# laser-tag.net
KiCad netlist of a schematic drawn in EAGLE
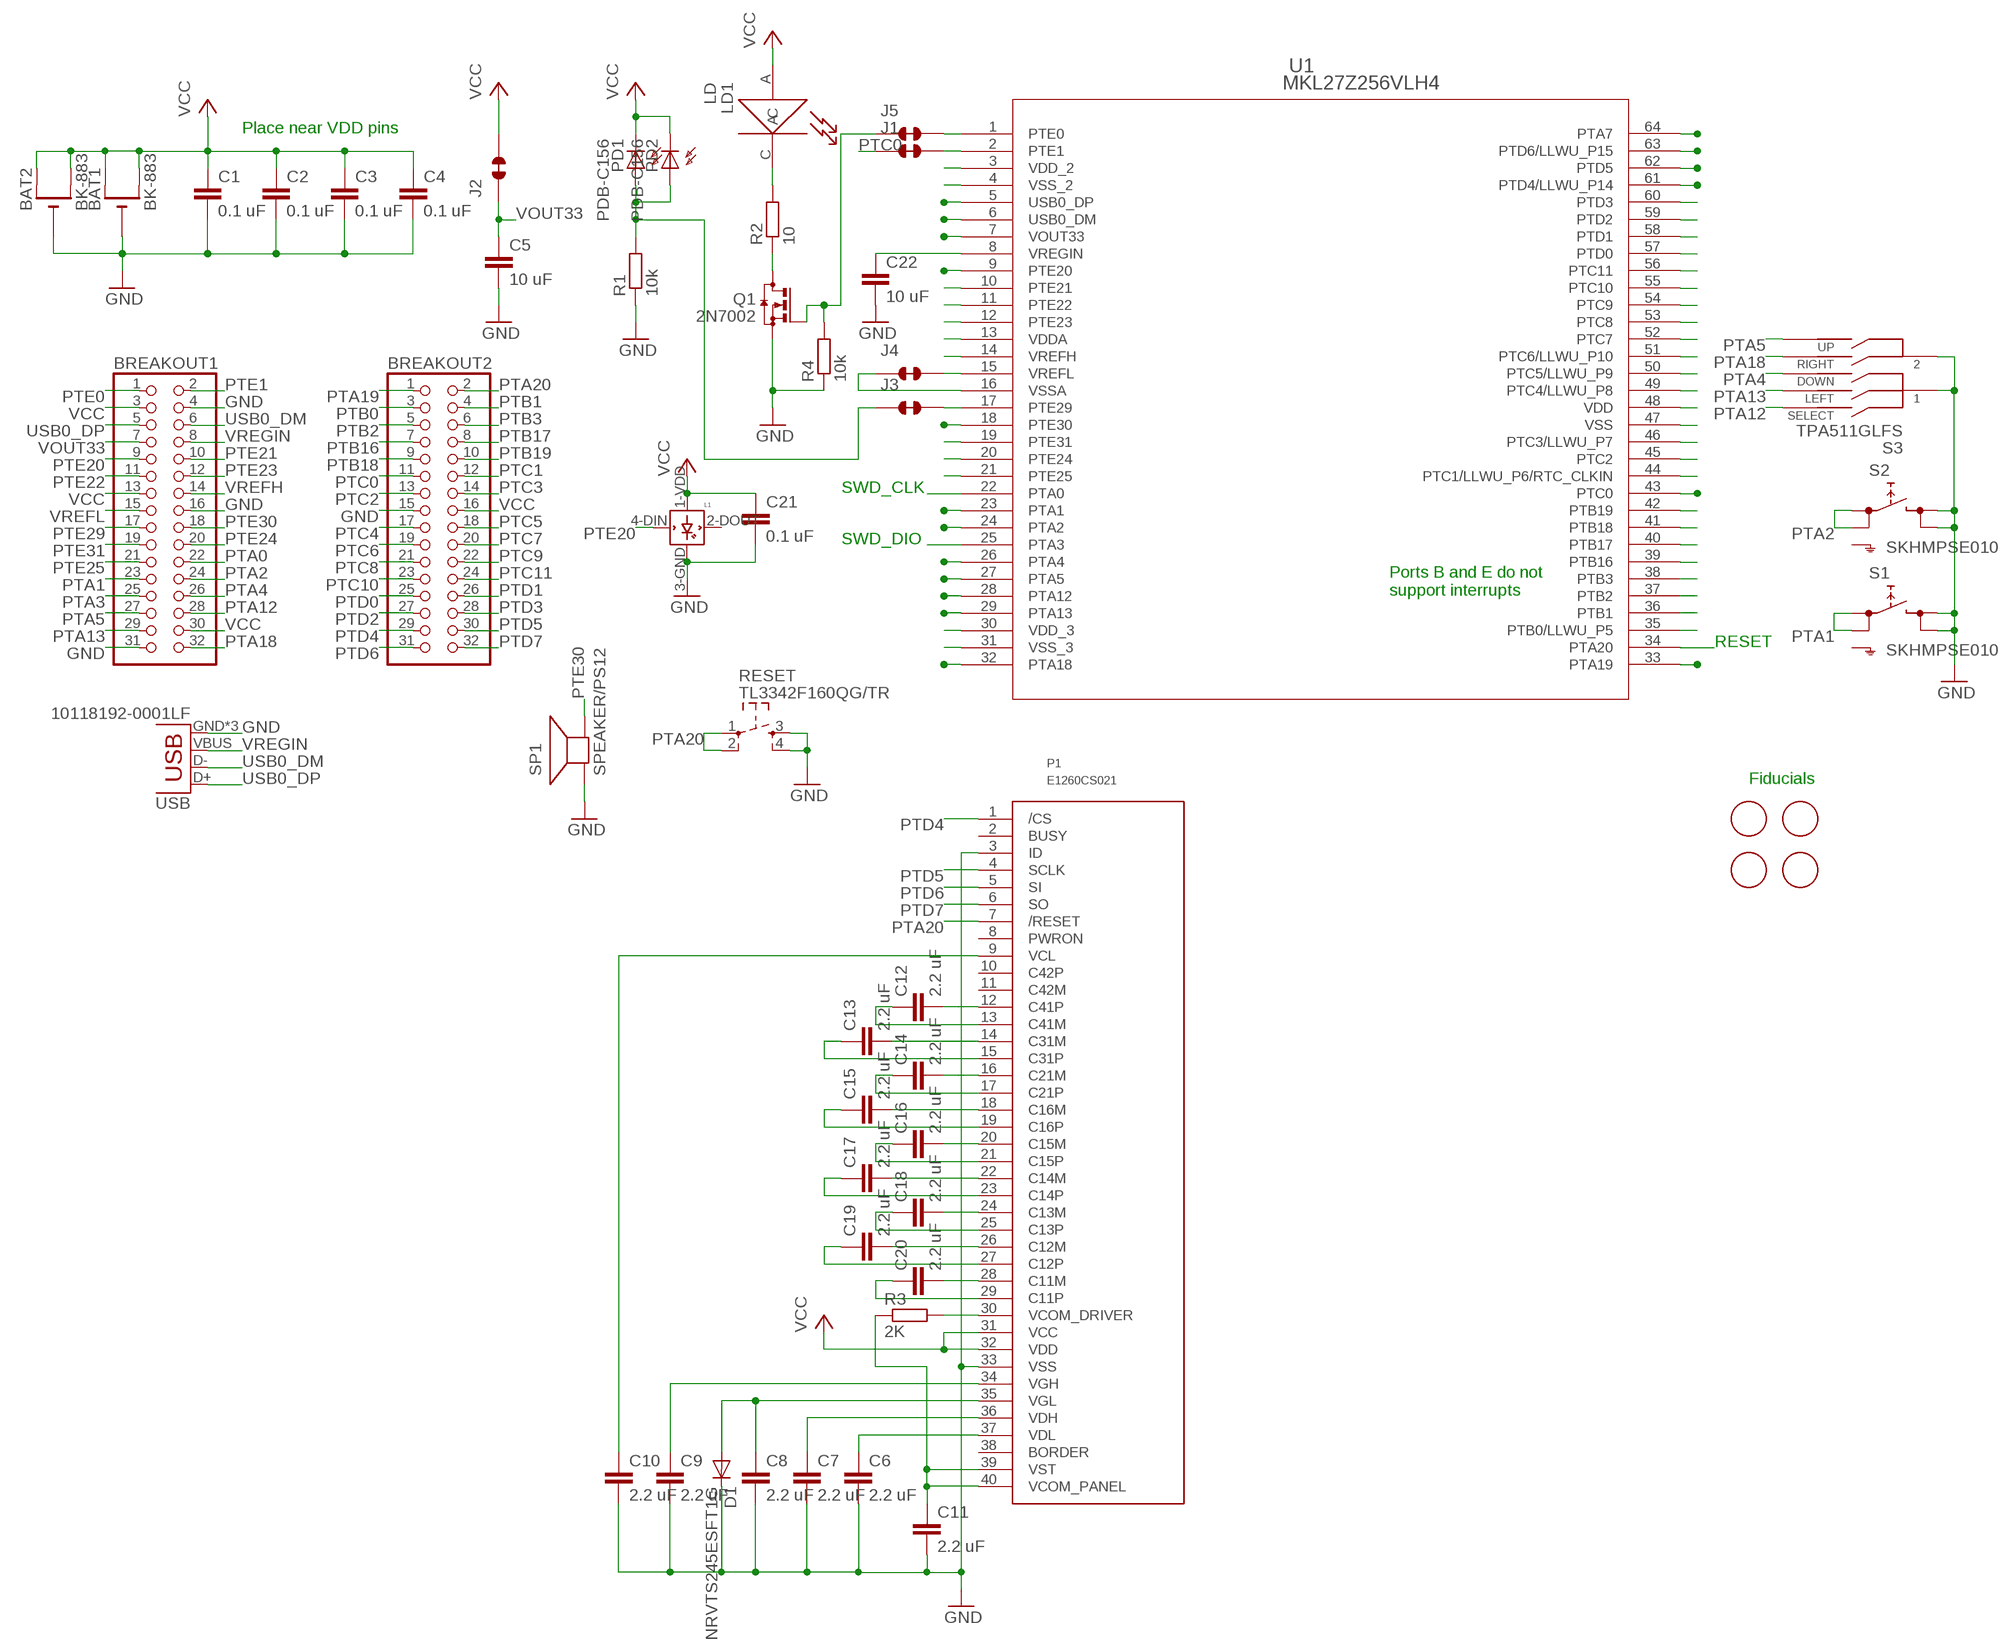
[diagram p0: schematic, sheet 1]

(export (version "E")
  (design (tool "Eeschema 10.0.6"))
  (components
    (comp (ref "BAT1")
      (value "BK-883")
      (footprint "eagle-import:CR2032-SMD")
      (libsource (lib "eagle-import") (part "CR2032SMT"))
    )
    (comp (ref "BAT2")
      (value "BK-883")
      (footprint "eagle-import:CR2032-SMD")
      (libsource (lib "eagle-import") (part "CR2032SMT"))
    )
    (comp (ref "BREAKOUT1")
      (value "PINHD-2X16")
      (footprint "eagle-import:2X16")
      (libsource (lib "eagle-import") (part "PINHD-2X16"))
    )
    (comp (ref "BREAKOUT2")
      (value "PINHD-2X16")
      (footprint "eagle-import:2X16")
      (libsource (lib "eagle-import") (part "PINHD-2X16"))
    )
    (comp (ref "C1")
      (value "0.1 uF")
      (footprint "eagle-import:C0603K")
      (libsource (lib "eagle-import") (part "C-EUC0603K"))
    )
    (comp (ref "C2")
      (value "0.1 uF")
      (footprint "eagle-import:C0603K")
      (libsource (lib "eagle-import") (part "C-EUC0603K"))
    )
    (comp (ref "C3")
      (value "0.1 uF")
      (footprint "eagle-import:C0603K")
      (libsource (lib "eagle-import") (part "C-EUC0603K"))
    )
    (comp (ref "C4")
      (value "0.1 uF")
      (footprint "eagle-import:C0603K")
      (libsource (lib "eagle-import") (part "C-EUC0603K"))
    )
    (comp (ref "C5")
      (value "10 uF")
      (footprint "eagle-import:C0603K")
      (libsource (lib "eagle-import") (part "C-EUC0603K"))
    )
    (comp (ref "C6")
      (value "2.2 uF")
      (footprint "eagle-import:C0603K")
      (libsource (lib "eagle-import") (part "C-EUC0603K"))
    )
    (comp (ref "C7")
      (value "2.2 uF")
      (footprint "eagle-import:C0603K")
      (libsource (lib "eagle-import") (part "C-EUC0603K"))
    )
    (comp (ref "C8")
      (value "2.2 uF")
      (footprint "eagle-import:C0603K")
      (libsource (lib "eagle-import") (part "C-EUC0603K"))
    )
    (comp (ref "C9")
      (value "2.2 uF")
      (footprint "eagle-import:C0603K")
      (libsource (lib "eagle-import") (part "C-EUC0603K"))
    )
    (comp (ref "C10")
      (value "2.2 uF")
      (footprint "eagle-import:C0603K")
      (libsource (lib "eagle-import") (part "C-EUC0603K"))
    )
    (comp (ref "C11")
      (value "2.2 uF")
      (footprint "eagle-import:C0603K")
      (libsource (lib "eagle-import") (part "C-EUC0603K"))
    )
    (comp (ref "C12")
      (value "2.2 uF")
      (footprint "eagle-import:C0603K")
      (libsource (lib "eagle-import") (part "C-EUC0603K"))
    )
    (comp (ref "C13")
      (value "2.2 uF")
      (footprint "eagle-import:C0603K")
      (libsource (lib "eagle-import") (part "C-EUC0603K"))
    )
    (comp (ref "C14")
      (value "2.2 uF")
      (footprint "eagle-import:C0603K")
      (libsource (lib "eagle-import") (part "C-EUC0603K"))
    )
    (comp (ref "C15")
      (value "2.2 uF")
      (footprint "eagle-import:C0603K")
      (libsource (lib "eagle-import") (part "C-EUC0603K"))
    )
    (comp (ref "C16")
      (value "2.2 uF")
      (footprint "eagle-import:C0603K")
      (libsource (lib "eagle-import") (part "C-EUC0603K"))
    )
    (comp (ref "C17")
      (value "2.2 uF")
      (footprint "eagle-import:C0603K")
      (libsource (lib "eagle-import") (part "C-EUC0603K"))
    )
    (comp (ref "C18")
      (value "2.2 uF")
      (footprint "eagle-import:C0603K")
      (libsource (lib "eagle-import") (part "C-EUC0603K"))
    )
    (comp (ref "C19")
      (value "2.2 uF")
      (footprint "eagle-import:C0603K")
      (libsource (lib "eagle-import") (part "C-EUC0603K"))
    )
    (comp (ref "C20")
      (value "2.2 uF")
      (footprint "eagle-import:C0603K")
      (libsource (lib "eagle-import") (part "C-EUC0603K"))
    )
    (comp (ref "C21")
      (value "0.1 uF")
      (footprint "eagle-import:C0603K")
      (libsource (lib "eagle-import") (part "C-EUC0603K"))
    )
    (comp (ref "C22")
      (value "10 uF")
      (footprint "eagle-import:C0603K")
      (libsource (lib "eagle-import") (part "C-EUC0603K"))
    )
    (comp (ref "D1")
      (value "NRVTS245ESFT1G")
      (footprint "eagle-import:SOD-123_MINI-SMA")
      (libsource (lib "eagle-import") (part "CGRM400-G1"))
    )
    (comp (ref "J1")
      (value "JUMPER_SOLDER_1X2_CLOSED")
      (footprint "eagle-import:JUMPER_SOLDER_1X2_CLOSED")
      (libsource (lib "eagle-import") (part "JUMPER_SOLDER_1X2_CLOSED"))
    )
    (comp (ref "J2")
      (value "JUMPER_SOLDER_1X2_CLOSED")
      (footprint "eagle-import:JUMPER_SOLDER_1X2_CLOSED")
      (libsource (lib "eagle-import") (part "JUMPER_SOLDER_1X2_CLOSED"))
    )
    (comp (ref "J3")
      (value "JUMPER_SOLDER_1X2_CLOSED")
      (footprint "eagle-import:JUMPER_SOLDER_1X2_CLOSED")
      (libsource (lib "eagle-import") (part "JUMPER_SOLDER_1X2_CLOSED"))
    )
    (comp (ref "J4")
      (value "JUMPER_SOLDER_1X2_CLOSED")
      (footprint "eagle-import:JUMPER_SOLDER_1X2_CLOSED")
      (libsource (lib "eagle-import") (part "JUMPER_SOLDER_1X2_CLOSED"))
    )
    (comp (ref "J5")
      (value "JUMPER_SOLDER_1X2_CLOSED")
      (footprint "eagle-import:JUMPER_SOLDER_1X2_CLOSED")
      (libsource (lib "eagle-import") (part "JUMPER_SOLDER_1X2_CLOSED"))
    )
    (comp (ref "L1")
      (value "WS2812B")
      (footprint "eagle-import:WS2812B")
      (libsource (lib "eagle-import") (part "WS2812B"))
    )
    (comp (ref "LD1")
      (value "LD")
      (footprint "eagle-import:LD-FLUSH-WITH-JUMPER")
      (libsource (lib "eagle-import") (part "LD"))
    )
    (comp (ref "P1")
      (value "E1260CS021")
      (footprint "eagle-import:E1260CS021_SLOT")
      (libsource (lib "eagle-import") (part "E1260CS021"))
    )
    (comp (ref "PD1")
      (value "PDB-C156")
      (footprint "eagle-import:PDB-C156-FLUSH")
      (libsource (lib "eagle-import") (part "PDB-C156"))
    )
    (comp (ref "PD2")
      (value "PDB-C156")
      (footprint "eagle-import:PDB-C156-FLUSH")
      (libsource (lib "eagle-import") (part "PDB-C156"))
    )
    (comp (ref "Q1")
      (value "2N7002")
      (footprint "eagle-import:SOT23")
      (libsource (lib "eagle-import") (part "BSS123"))
    )
    (comp (ref "R1")
      (value "10k")
      (footprint "eagle-import:R0603")
      (libsource (lib "eagle-import") (part "R-EU_R0603"))
    )
    (comp (ref "R2")
      (value "10")
      (footprint "eagle-import:R0603")
      (libsource (lib "eagle-import") (part "R-EU_R0603"))
    )
    (comp (ref "R3")
      (value "2K")
      (footprint "eagle-import:R0603")
      (libsource (lib "eagle-import") (part "R-EU_R0603"))
    )
    (comp (ref "R4")
      (value "10k")
      (footprint "eagle-import:R0603")
      (libsource (lib "eagle-import") (part "R-EU_R0603"))
    )
    (comp (ref "RESET")
      (value "TL3342F160QG/TR")
      (footprint "eagle-import:SW_TACT_SMALL")
      (libsource (lib "eagle-import") (part "SW_TACT_4P"))
    )
    (comp (ref "S1")
      (value "SKHMPSE010")
      (footprint "eagle-import:SKHMPXE010")
      (libsource (lib "eagle-import") (part "SKHMPE010S"))
    )
    (comp (ref "S2")
      (value "SKHMPSE010")
      (footprint "eagle-import:SKHMPXE010")
      (libsource (lib "eagle-import") (part "SKHMPE010S"))
    )
    (comp (ref "S3")
      (value "TPA511GLFS")
      (footprint "eagle-import:TPA511GLFS")
      (libsource (lib "eagle-import") (part "TPA511GLFS"))
    )
    (comp (ref "SP1")
      (value "SPEAKER/PS12")
      (footprint "eagle-import:PS12")
      (libsource (lib "eagle-import") (part "SPEAKER/PS12"))
    )
    (comp (ref "U$1")
      (value "FIDUCIAL")
      (footprint "eagle-import:FIDUCIAL_1MM")
      (libsource (lib "eagle-import") (part "FIDUCIAL"))
    )
    (comp (ref "U$2")
      (value "FIDUCIAL")
      (footprint "eagle-import:FIDUCIAL_1MM")
      (libsource (lib "eagle-import") (part "FIDUCIAL"))
    )
    (comp (ref "U$3")
      (value "FIDUCIAL")
      (footprint "eagle-import:FIDUCIAL_1MM")
      (libsource (lib "eagle-import") (part "FIDUCIAL"))
    )
    (comp (ref "U$4")
      (value "FIDUCIAL")
      (footprint "eagle-import:FIDUCIAL_1MM")
      (libsource (lib "eagle-import") (part "FIDUCIAL"))
    )
    (comp (ref "U1")
      (value "MKL27Z256VLH4")
      (footprint "eagle-import:LQFP-64_10X10X1.6")
      (fields (field (name "MANUFACTURER_PART_NUMBER") "mkl27z256vlh4"))
      (libsource (lib "eagle-import") (part "MKL27Z256VLH4"))
    )
    (comp (ref "USB")
      (value "10118192-0001LF")
      (footprint "eagle-import:USB-MICROB")
      (libsource (lib "eagle-import") (part "USB-MICROB"))
    )
  )
  (nets
    (net (code "1") (name "/PTA0") (class "Default")
      (node (ref "BREAKOUT1") (pin "22") (pinfunction "22_22") (pintype "passive"))
      (node (ref "U1") (pin "22") (pinfunction "PTA0_22") (pintype "bidirectional"))
    )
    (net (code "2") (name "/PTA1") (class "Default")
      (node (ref "BREAKOUT1") (pin "23") (pinfunction "23_23") (pintype "passive"))
      (node (ref "S1") (pin "1") (pinfunction "1.1_1") (pintype "passive"))
      (node (ref "S1") (pin "2") (pinfunction "1.2_2") (pintype "passive"))
      (node (ref "U1") (pin "23") (pinfunction "PTA1_23") (pintype "bidirectional"))
    )
    (net (code "3") (name "/PTA2") (class "Default")
      (node (ref "BREAKOUT1") (pin "24") (pinfunction "24_24") (pintype "passive"))
      (node (ref "S2") (pin "1") (pinfunction "1.1_1") (pintype "passive"))
      (node (ref "S2") (pin "2") (pinfunction "1.2_2") (pintype "passive"))
      (node (ref "U1") (pin "24") (pinfunction "PTA2_24") (pintype "bidirectional"))
    )
    (net (code "4") (name "/PTA3") (class "Default")
      (node (ref "BREAKOUT1") (pin "25") (pinfunction "25_25") (pintype "passive"))
      (node (ref "U1") (pin "25") (pinfunction "PTA3_25") (pintype "bidirectional"))
    )
    (net (code "5") (name "/PTA4") (class "Default")
      (node (ref "BREAKOUT1") (pin "26") (pinfunction "26_26") (pintype "passive"))
      (node (ref "S3") (pin "4") (pinfunction "DOWN_4") (pintype "bidirectional"))
      (node (ref "U1") (pin "26") (pinfunction "PTA4_26") (pintype "bidirectional"))
    )
    (net (code "6") (name "/PTA5") (class "Default")
      (node (ref "BREAKOUT1") (pin "27") (pinfunction "27_27") (pintype "passive"))
      (node (ref "S3") (pin "3") (pinfunction "UP_3") (pintype "bidirectional"))
      (node (ref "U1") (pin "27") (pinfunction "PTA5_27") (pintype "bidirectional"))
    )
    (net (code "7") (name "/PTA12") (class "Default")
      (node (ref "BREAKOUT1") (pin "28") (pinfunction "28_28") (pintype "passive"))
      (node (ref "S3") (pin "5") (pinfunction "SELECT_5") (pintype "bidirectional"))
      (node (ref "U1") (pin "28") (pinfunction "PTA12_28") (pintype "bidirectional"))
    )
    (net (code "8") (name "/PTA13") (class "Default")
      (node (ref "BREAKOUT1") (pin "29") (pinfunction "29_29") (pintype "passive"))
      (node (ref "S3") (pin "7") (pinfunction "LEFT_7") (pintype "bidirectional"))
      (node (ref "U1") (pin "29") (pinfunction "PTA13_29") (pintype "bidirectional"))
    )
    (net (code "9") (name "/PTA18") (class "Default")
      (node (ref "BREAKOUT1") (pin "32") (pinfunction "32_32") (pintype "passive"))
      (node (ref "S3") (pin "6") (pinfunction "RIGHT_6") (pintype "bidirectional"))
      (node (ref "U1") (pin "32") (pinfunction "PTA18_32") (pintype "bidirectional"))
    )
    (net (code "10") (name "/PTA19") (class "Default")
      (node (ref "BREAKOUT2") (pin "1") (pinfunction "1_1") (pintype "passive"))
      (node (ref "U1") (pin "33") (pinfunction "PTA19_33") (pintype "bidirectional"))
    )
    (net (code "11") (name "/PTA20") (class "Default")
      (node (ref "BREAKOUT2") (pin "2") (pinfunction "2_2") (pintype "passive"))
      (node (ref "P1") (pin "7") (pinfunction "/RESET_7") (pintype "input"))
      (node (ref "RESET") (pin "1") (pinfunction "1_1") (pintype "passive"))
      (node (ref "RESET") (pin "2") (pinfunction "2_2") (pintype "passive"))
      (node (ref "U1") (pin "34") (pinfunction "PTA20_34") (pintype "bidirectional"))
    )
    (net (code "12") (name "/PTB0") (class "Default")
      (node (ref "BREAKOUT2") (pin "3") (pinfunction "3_3") (pintype "passive"))
      (node (ref "U1") (pin "35") (pinfunction "PTB0/LLWU_P5_35") (pintype "bidirectional"))
    )
    (net (code "13") (name "/PTB1") (class "Default")
      (node (ref "BREAKOUT2") (pin "4") (pinfunction "4_4") (pintype "passive"))
      (node (ref "U1") (pin "36") (pinfunction "PTB1_36") (pintype "bidirectional"))
    )
    (net (code "14") (name "/PTB2") (class "Default")
      (node (ref "BREAKOUT2") (pin "5") (pinfunction "5_5") (pintype "passive"))
      (node (ref "U1") (pin "37") (pinfunction "PTB2_37") (pintype "bidirectional"))
    )
    (net (code "15") (name "/PTB3") (class "Default")
      (node (ref "BREAKOUT2") (pin "6") (pinfunction "6_6") (pintype "passive"))
      (node (ref "U1") (pin "38") (pinfunction "PTB3_38") (pintype "bidirectional"))
    )
    (net (code "16") (name "/PTB16") (class "Default")
      (node (ref "BREAKOUT2") (pin "7") (pinfunction "7_7") (pintype "passive"))
      (node (ref "U1") (pin "39") (pinfunction "PTB16_39") (pintype "bidirectional"))
    )
    (net (code "17") (name "/PTB17") (class "Default")
      (node (ref "BREAKOUT2") (pin "8") (pinfunction "8_8") (pintype "passive"))
      (node (ref "U1") (pin "40") (pinfunction "PTB17_40") (pintype "bidirectional"))
    )
    (net (code "18") (name "/PTB18") (class "Default")
      (node (ref "BREAKOUT2") (pin "9") (pinfunction "9_9") (pintype "passive"))
      (node (ref "U1") (pin "41") (pinfunction "PTB18_41") (pintype "bidirectional"))
    )
    (net (code "19") (name "/PTB19") (class "Default")
      (node (ref "BREAKOUT2") (pin "10") (pinfunction "10_10") (pintype "passive"))
      (node (ref "U1") (pin "42") (pinfunction "PTB19_42") (pintype "bidirectional"))
    )
    (net (code "20") (name "/PTC0") (class "Default")
      (node (ref "BREAKOUT2") (pin "11") (pinfunction "11_11") (pintype "passive"))
      (node (ref "J1") (pin "1") (pinfunction "1_1") (pintype "passive"))
      (node (ref "U1") (pin "43") (pinfunction "PTC0_43") (pintype "bidirectional"))
    )
    (net (code "21") (name "/PTC1") (class "Default")
      (node (ref "BREAKOUT2") (pin "12") (pinfunction "12_12") (pintype "passive"))
      (node (ref "U1") (pin "44") (pinfunction "PTC1/LLWU_P6/RTC_CLKIN_44") (pintype "bidirectional"))
    )
    (net (code "22") (name "/PTC2") (class "Default")
      (node (ref "BREAKOUT2") (pin "13") (pinfunction "13_13") (pintype "passive"))
      (node (ref "U1") (pin "45") (pinfunction "PTC2_45") (pintype "bidirectional"))
    )
    (net (code "23") (name "/PTC3") (class "Default")
      (node (ref "BREAKOUT2") (pin "14") (pinfunction "14_14") (pintype "passive"))
      (node (ref "U1") (pin "46") (pinfunction "PTC3/LLWU_P7_46") (pintype "bidirectional"))
    )
    (net (code "24") (name "/PTC4") (class "Default")
      (node (ref "BREAKOUT2") (pin "17") (pinfunction "17_17") (pintype "passive"))
      (node (ref "U1") (pin "49") (pinfunction "PTC4/LLWU_P8_49") (pintype "bidirectional"))
    )
    (net (code "25") (name "/PTC5") (class "Default")
      (node (ref "BREAKOUT2") (pin "18") (pinfunction "18_18") (pintype "passive"))
      (node (ref "U1") (pin "50") (pinfunction "PTC5/LLWU_P9_50") (pintype "bidirectional"))
    )
    (net (code "26") (name "/PTC6") (class "Default")
      (node (ref "BREAKOUT2") (pin "19") (pinfunction "19_19") (pintype "passive"))
      (node (ref "U1") (pin "51") (pinfunction "PTC6/LLWU_P10_51") (pintype "bidirectional"))
    )
    (net (code "27") (name "/PTC7") (class "Default")
      (node (ref "BREAKOUT2") (pin "20") (pinfunction "20_20") (pintype "passive"))
      (node (ref "U1") (pin "52") (pinfunction "PTC7_52") (pintype "bidirectional"))
    )
    (net (code "28") (name "/PTC8") (class "Default")
      (node (ref "BREAKOUT2") (pin "21") (pinfunction "21_21") (pintype "passive"))
      (node (ref "U1") (pin "53") (pinfunction "PTC8_53") (pintype "bidirectional"))
    )
    (net (code "29") (name "/PTC9") (class "Default")
      (node (ref "BREAKOUT2") (pin "22") (pinfunction "22_22") (pintype "passive"))
      (node (ref "U1") (pin "54") (pinfunction "PTC9_54") (pintype "bidirectional"))
    )
    (net (code "30") (name "/PTC10") (class "Default")
      (node (ref "BREAKOUT2") (pin "23") (pinfunction "23_23") (pintype "passive"))
      (node (ref "U1") (pin "55") (pinfunction "PTC10_55") (pintype "bidirectional"))
    )
    (net (code "31") (name "/PTC11") (class "Default")
      (node (ref "BREAKOUT2") (pin "24") (pinfunction "24_24") (pintype "passive"))
      (node (ref "U1") (pin "56") (pinfunction "PTC11_56") (pintype "bidirectional"))
    )
    (net (code "32") (name "/PTD0") (class "Default")
      (node (ref "BREAKOUT2") (pin "25") (pinfunction "25_25") (pintype "passive"))
      (node (ref "U1") (pin "57") (pinfunction "PTD0_57") (pintype "bidirectional"))
    )
    (net (code "33") (name "/PTD1") (class "Default")
      (node (ref "BREAKOUT2") (pin "26") (pinfunction "26_26") (pintype "passive"))
      (node (ref "U1") (pin "58") (pinfunction "PTD1_58") (pintype "bidirectional"))
    )
    (net (code "34") (name "/PTD2") (class "Default")
      (node (ref "BREAKOUT2") (pin "27") (pinfunction "27_27") (pintype "passive"))
      (node (ref "U1") (pin "59") (pinfunction "PTD2_59") (pintype "bidirectional"))
    )
    (net (code "35") (name "/PTD3") (class "Default")
      (node (ref "BREAKOUT2") (pin "28") (pinfunction "28_28") (pintype "passive"))
      (node (ref "U1") (pin "60") (pinfunction "PTD3_60") (pintype "bidirectional"))
    )
    (net (code "36") (name "/PTD4") (class "Default")
      (node (ref "BREAKOUT2") (pin "29") (pinfunction "29_29") (pintype "passive"))
      (node (ref "P1") (pin "1") (pinfunction "/CS_1") (pintype "input"))
      (node (ref "U1") (pin "61") (pinfunction "PTD4/LLWU_P14_61") (pintype "bidirectional"))
    )
    (net (code "37") (name "/PTD5") (class "Default")
      (node (ref "BREAKOUT2") (pin "30") (pinfunction "30_30") (pintype "passive"))
      (node (ref "P1") (pin "4") (pinfunction "SCLK_4") (pintype "input"))
      (node (ref "U1") (pin "62") (pinfunction "PTD5_62") (pintype "bidirectional"))
    )
    (net (code "38") (name "/PTD6") (class "Default")
      (node (ref "BREAKOUT2") (pin "31") (pinfunction "31_31") (pintype "passive"))
      (node (ref "P1") (pin "5") (pinfunction "SI_5") (pintype "input"))
      (node (ref "U1") (pin "63") (pinfunction "PTD6/LLWU_P15_63") (pintype "bidirectional"))
    )
    (net (code "39") (name "/PTD7") (class "Default")
      (node (ref "BREAKOUT2") (pin "32") (pinfunction "32_32") (pintype "passive"))
      (node (ref "P1") (pin "6") (pinfunction "SO_6") (pintype "output"))
      (node (ref "U1") (pin "64") (pinfunction "PTA7_64") (pintype "bidirectional"))
    )
    (net (code "40") (name "/PTE0") (class "Default")
      (node (ref "BREAKOUT1") (pin "1") (pinfunction "1_1") (pintype "passive"))
      (node (ref "J5") (pin "2") (pinfunction "2_2") (pintype "passive"))
      (node (ref "U1") (pin "1") (pinfunction "PTE0_1") (pintype "bidirectional"))
    )
    (net (code "41") (name "/PTE1") (class "Default")
      (node (ref "BREAKOUT1") (pin "2") (pinfunction "2_2") (pintype "passive"))
      (node (ref "J1") (pin "2") (pinfunction "2_2") (pintype "passive"))
      (node (ref "U1") (pin "2") (pinfunction "PTE1_2") (pintype "bidirectional"))
    )
    (net (code "42") (name "/PTE20") (class "Default")
      (node (ref "BREAKOUT1") (pin "9") (pinfunction "9_9") (pintype "passive"))
      (node (ref "L1") (pin "4-DIN") (pinfunction "DIN_4-DIN") (pintype "input"))
      (node (ref "U1") (pin "9") (pinfunction "PTE20_9") (pintype "bidirectional"))
    )
    (net (code "43") (name "/PTE21") (class "Default")
      (node (ref "BREAKOUT1") (pin "10") (pinfunction "10_10") (pintype "passive"))
      (node (ref "U1") (pin "10") (pinfunction "PTE21_10") (pintype "bidirectional"))
    )
    (net (code "44") (name "/PTE22") (class "Default")
      (node (ref "BREAKOUT1") (pin "11") (pinfunction "11_11") (pintype "passive"))
      (node (ref "U1") (pin "11") (pinfunction "PTE22_11") (pintype "bidirectional"))
    )
    (net (code "45") (name "/PTE23") (class "Default")
      (node (ref "BREAKOUT1") (pin "12") (pinfunction "12_12") (pintype "passive"))
      (node (ref "U1") (pin "12") (pinfunction "PTE23_12") (pintype "bidirectional"))
    )
    (net (code "46") (name "/PTE24") (class "Default")
      (node (ref "BREAKOUT1") (pin "20") (pinfunction "20_20") (pintype "passive"))
      (node (ref "U1") (pin "20") (pinfunction "PTE24_20") (pintype "bidirectional"))
    )
    (net (code "47") (name "/PTE25") (class "Default")
      (node (ref "BREAKOUT1") (pin "21") (pinfunction "21_21") (pintype "passive"))
      (node (ref "U1") (pin "21") (pinfunction "PTE25_21") (pintype "bidirectional"))
    )
    (net (code "48") (name "/PTE29") (class "Default")
      (node (ref "BREAKOUT1") (pin "17") (pinfunction "17_17") (pintype "passive"))
      (node (ref "J3") (pin "2") (pinfunction "2_2") (pintype "passive"))
      (node (ref "U1") (pin "17") (pinfunction "PTE29_17") (pintype "bidirectional"))
    )
    (net (code "49") (name "/PTE30") (class "Default")
      (node (ref "BREAKOUT1") (pin "18") (pinfunction "18_18") (pintype "passive"))
      (node (ref "SP1") (pin "P$2") (pinfunction "-_P$2") (pintype "passive"))
      (node (ref "U1") (pin "18") (pinfunction "PTE30_18") (pintype "bidirectional"))
    )
    (net (code "50") (name "/PTE31") (class "Default")
      (node (ref "BREAKOUT1") (pin "19") (pinfunction "19_19") (pintype "passive"))
      (node (ref "U1") (pin "19") (pinfunction "PTE31_19") (pintype "bidirectional"))
    )
    (net (code "51") (name "/USB0_DM") (class "Default")
      (node (ref "BREAKOUT1") (pin "6") (pinfunction "6_6") (pintype "passive"))
      (node (ref "U1") (pin "6") (pinfunction "USB0_DM_6") (pintype "passive"))
      (node (ref "USB") (pin "D-") (pinfunction "D-_D-") (pintype "bidirectional"))
    )
    (net (code "52") (name "/USB0_DP") (class "Default")
      (node (ref "BREAKOUT1") (pin "5") (pinfunction "5_5") (pintype "passive"))
      (node (ref "U1") (pin "5") (pinfunction "USB0_DP_5") (pintype "passive"))
      (node (ref "USB") (pin "D+") (pinfunction "D+_D+") (pintype "bidirectional"))
    )
    (net (code "53") (name "/VOUT33") (class "Default")
      (node (ref "BREAKOUT1") (pin "7") (pinfunction "7_7") (pintype "passive"))
      (node (ref "C5") (pin "1") (pinfunction "1_1") (pintype "passive"))
      (node (ref "J2") (pin "1") (pinfunction "1_1") (pintype "passive"))
      (node (ref "U1") (pin "7") (pinfunction "VOUT33_7") (pintype "output"))
    )
    (net (code "54") (name "/VREFH") (class "Default")
      (node (ref "BREAKOUT1") (pin "14") (pinfunction "14_14") (pintype "passive"))
      (node (ref "U1") (pin "14") (pinfunction "VREFH_14") (pintype "power_in"))
    )
    (net (code "55") (name "/VREFL") (class "Default")
      (node (ref "BREAKOUT1") (pin "15") (pinfunction "15_15") (pintype "passive"))
      (node (ref "J4") (pin "2") (pinfunction "2_2") (pintype "passive"))
      (node (ref "U1") (pin "15") (pinfunction "VREFL_15") (pintype "power_in"))
    )
    (net (code "56") (name "/VREGIN") (class "Default")
      (node (ref "BREAKOUT1") (pin "8") (pinfunction "8_8") (pintype "passive"))
      (node (ref "C22") (pin "1") (pinfunction "1_1") (pintype "passive"))
      (node (ref "U1") (pin "8") (pinfunction "VREGIN_8") (pintype "input"))
      (node (ref "USB") (pin "VBUS") (pinfunction "VBUS_VBUS") (pintype "bidirectional"))
    )
    (net (code "57") (name "GND") (class "Default")
      (node (ref "BAT1") (pin "-") (pinfunction "-_-") (pintype "passive"))
      (node (ref "BAT2") (pin "-") (pinfunction "-_-") (pintype "passive"))
      (node (ref "BREAKOUT1") (pin "16") (pinfunction "16_16") (pintype "passive"))
      (node (ref "BREAKOUT1") (pin "31") (pinfunction "31_31") (pintype "passive"))
      (node (ref "BREAKOUT1") (pin "4") (pinfunction "4_4") (pintype "passive"))
      (node (ref "BREAKOUT2") (pin "15") (pinfunction "15_15") (pintype "passive"))
      (node (ref "C1") (pin "2") (pinfunction "2_2") (pintype "passive"))
      (node (ref "C10") (pin "2") (pinfunction "2_2") (pintype "passive"))
      (node (ref "C11") (pin "2") (pinfunction "2_2") (pintype "passive"))
      (node (ref "C2") (pin "2") (pinfunction "2_2") (pintype "passive"))
      (node (ref "C21") (pin "2") (pinfunction "2_2") (pintype "passive"))
      (node (ref "C22") (pin "2") (pinfunction "2_2") (pintype "passive"))
      (node (ref "C3") (pin "2") (pinfunction "2_2") (pintype "passive"))
      (node (ref "C4") (pin "2") (pinfunction "2_2") (pintype "passive"))
      (node (ref "C5") (pin "2") (pinfunction "2_2") (pintype "passive"))
      (node (ref "C6") (pin "2") (pinfunction "2_2") (pintype "passive"))
      (node (ref "C7") (pin "2") (pinfunction "2_2") (pintype "passive"))
      (node (ref "C8") (pin "2") (pinfunction "2_2") (pintype "passive"))
      (node (ref "C9") (pin "2") (pinfunction "2_2") (pintype "passive"))
      (node (ref "D1") (pin "C") (pinfunction "C_C") (pintype "passive"))
      (node (ref "J4") (pin "1") (pinfunction "1_1") (pintype "passive"))
      (node (ref "L1") (pin "3-GND") (pinfunction "GND_3-GND") (pintype "bidirectional"))
      (node (ref "P1") (pin "3") (pinfunction "ID_3") (pintype "input"))
      (node (ref "P1") (pin "33") (pinfunction "VSS_33") (pintype "power_in"))
      (node (ref "Q1") (pin "2") (pinfunction "S_2") (pintype "passive"))
      (node (ref "R1") (pin "1") (pinfunction "1_1") (pintype "passive"))
      (node (ref "R4") (pin "1") (pinfunction "1_1") (pintype "passive"))
      (node (ref "RESET") (pin "3") (pinfunction "3_3") (pintype "passive"))
      (node (ref "RESET") (pin "4") (pinfunction "4_4") (pintype "passive"))
      (node (ref "S1") (pin "3") (pinfunction "2.1_3") (pintype "passive"))
      (node (ref "S1") (pin "4") (pinfunction "2.2_4") (pintype "passive"))
      (node (ref "S2") (pin "3") (pinfunction "2.1_3") (pintype "passive"))
      (node (ref "S2") (pin "4") (pinfunction "2.2_4") (pintype "passive"))
      (node (ref "S3") (pin "1") (pinfunction "1_1") (pintype "bidirectional"))
      (node (ref "S3") (pin "2") (pinfunction "2_2") (pintype "bidirectional"))
      (node (ref "SP1") (pin "P$1") (pinfunction "+_P$1") (pintype "passive"))
      (node (ref "U1") (pin "16") (pinfunction "VSSA_16") (pintype "power_in"))
      (node (ref "U1") (pin "31") (pinfunction "VSS_3_31") (pintype "power_in"))
      (node (ref "U1") (pin "4") (pinfunction "VSS_2_4") (pintype "power_in"))
      (node (ref "U1") (pin "47") (pinfunction "VSS_47") (pintype "power_in"))
      (node (ref "USB") (pin "GND") (pinfunction "GND_GND") (pintype "bidirectional"))
      (node (ref "USB") (pin "MT1") (pinfunction "GND_MT1") (pintype "bidirectional"))
      (node (ref "USB") (pin "MT2") (pinfunction "GND_MT2") (pintype "bidirectional"))
    )
    (net (code "58") (name "Net-(J3-Pad1)") (class "Default")
      (node (ref "J3") (pin "1") (pinfunction "1_1") (pintype "passive"))
      (node (ref "PD1") (pin "A") (pinfunction "A_A") (pintype "passive"))
      (node (ref "PD2") (pin "A") (pinfunction "A_A") (pintype "passive"))
      (node (ref "R1") (pin "2") (pinfunction "2_2") (pintype "passive"))
    )
    (net (code "59") (name "Net-(LD1-PadC)") (class "Default")
      (node (ref "LD1") (pin "C") (pinfunction "C_C") (pintype "passive"))
      (node (ref "R2") (pin "2") (pinfunction "2_2") (pintype "passive"))
    )
    (net (code "60") (name "Net-(P1-C11M)") (class "Default")
      (node (ref "C20") (pin "2") (pinfunction "2_2") (pintype "passive"))
      (node (ref "P1") (pin "28") (pinfunction "C11M_28") (pintype "passive"))
    )
    (net (code "61") (name "Net-(P1-C11P)") (class "Default")
      (node (ref "C20") (pin "1") (pinfunction "1_1") (pintype "passive"))
      (node (ref "P1") (pin "29") (pinfunction "C11P_29") (pintype "passive"))
    )
    (net (code "62") (name "Net-(P1-C12M)") (class "Default")
      (node (ref "C19") (pin "2") (pinfunction "2_2") (pintype "passive"))
      (node (ref "P1") (pin "26") (pinfunction "C12M_26") (pintype "passive"))
    )
    (net (code "63") (name "Net-(P1-C12P)") (class "Default")
      (node (ref "C19") (pin "1") (pinfunction "1_1") (pintype "passive"))
      (node (ref "P1") (pin "27") (pinfunction "C12P_27") (pintype "passive"))
    )
    (net (code "64") (name "Net-(P1-C13M)") (class "Default")
      (node (ref "C18") (pin "2") (pinfunction "2_2") (pintype "passive"))
      (node (ref "P1") (pin "24") (pinfunction "C13M_24") (pintype "passive"))
    )
    (net (code "65") (name "Net-(P1-C13P)") (class "Default")
      (node (ref "C18") (pin "1") (pinfunction "1_1") (pintype "passive"))
      (node (ref "P1") (pin "25") (pinfunction "C13P_25") (pintype "passive"))
    )
    (net (code "66") (name "Net-(P1-C14M)") (class "Default")
      (node (ref "C17") (pin "2") (pinfunction "2_2") (pintype "passive"))
      (node (ref "P1") (pin "22") (pinfunction "C14M_22") (pintype "passive"))
    )
    (net (code "67") (name "Net-(P1-C14P)") (class "Default")
      (node (ref "C17") (pin "1") (pinfunction "1_1") (pintype "passive"))
      (node (ref "P1") (pin "23") (pinfunction "C14P_23") (pintype "passive"))
    )
    (net (code "68") (name "Net-(P1-C15M)") (class "Default")
      (node (ref "C16") (pin "2") (pinfunction "2_2") (pintype "passive"))
      (node (ref "P1") (pin "20") (pinfunction "C15M_20") (pintype "passive"))
    )
    (net (code "69") (name "Net-(P1-C15P)") (class "Default")
      (node (ref "C16") (pin "1") (pinfunction "1_1") (pintype "passive"))
      (node (ref "P1") (pin "21") (pinfunction "C15P_21") (pintype "passive"))
    )
    (net (code "70") (name "Net-(P1-C16M)") (class "Default")
      (node (ref "C15") (pin "2") (pinfunction "2_2") (pintype "passive"))
      (node (ref "P1") (pin "18") (pinfunction "C16M_18") (pintype "passive"))
    )
    (net (code "71") (name "Net-(P1-C16P)") (class "Default")
      (node (ref "C15") (pin "1") (pinfunction "1_1") (pintype "passive"))
      (node (ref "P1") (pin "19") (pinfunction "C16P_19") (pintype "passive"))
    )
    (net (code "72") (name "Net-(P1-C21M)") (class "Default")
      (node (ref "C14") (pin "2") (pinfunction "2_2") (pintype "passive"))
      (node (ref "P1") (pin "16") (pinfunction "C21M_16") (pintype "passive"))
    )
    (net (code "73") (name "Net-(P1-C21P)") (class "Default")
      (node (ref "C14") (pin "1") (pinfunction "1_1") (pintype "passive"))
      (node (ref "P1") (pin "17") (pinfunction "C21P_17") (pintype "passive"))
    )
    (net (code "74") (name "Net-(P1-C31M)") (class "Default")
      (node (ref "C13") (pin "2") (pinfunction "2_2") (pintype "passive"))
      (node (ref "P1") (pin "14") (pinfunction "C31M_14") (pintype "passive"))
    )
    (net (code "75") (name "Net-(P1-C31P)") (class "Default")
      (node (ref "C13") (pin "1") (pinfunction "1_1") (pintype "passive"))
      (node (ref "P1") (pin "15") (pinfunction "C31P_15") (pintype "passive"))
    )
    (net (code "76") (name "Net-(P1-C41M)") (class "Default")
      (node (ref "C12") (pin "1") (pinfunction "1_1") (pintype "passive"))
      (node (ref "P1") (pin "13") (pinfunction "C41M_13") (pintype "passive"))
    )
    (net (code "77") (name "Net-(P1-C41P)") (class "Default")
      (node (ref "C12") (pin "2") (pinfunction "2_2") (pintype "passive"))
      (node (ref "P1") (pin "12") (pinfunction "C41P_12") (pintype "passive"))
    )
    (net (code "78") (name "Net-(P1-VCL)") (class "Default")
      (node (ref "C10") (pin "1") (pinfunction "1_1") (pintype "passive"))
      (node (ref "P1") (pin "9") (pinfunction "VCL_9") (pintype "passive"))
    )
    (net (code "79") (name "Net-(P1-VCOM_DRIVER)") (class "Default")
      (node (ref "P1") (pin "30") (pinfunction "VCOM_DRIVER_30") (pintype "passive"))
      (node (ref "R3") (pin "2") (pinfunction "2_2") (pintype "passive"))
    )
    (net (code "80") (name "Net-(P1-VCOM_PANEL)") (class "Default")
      (node (ref "C11") (pin "1") (pinfunction "1_1") (pintype "passive"))
      (node (ref "P1") (pin "39") (pinfunction "VST_39") (pintype "power_in"))
      (node (ref "P1") (pin "40") (pinfunction "VCOM_PANEL_40") (pintype "passive"))
      (node (ref "R3") (pin "1") (pinfunction "1_1") (pintype "passive"))
    )
    (net (code "81") (name "Net-(P1-VDH)") (class "Default")
      (node (ref "C7") (pin "1") (pinfunction "1_1") (pintype "passive"))
      (node (ref "P1") (pin "36") (pinfunction "VDH_36") (pintype "passive"))
    )
    (net (code "82") (name "Net-(P1-VDL)") (class "Default")
      (node (ref "C6") (pin "1") (pinfunction "1_1") (pintype "passive"))
      (node (ref "P1") (pin "37") (pinfunction "VDL_37") (pintype "passive"))
    )
    (net (code "83") (name "Net-(P1-VGH)") (class "Default")
      (node (ref "C9") (pin "1") (pinfunction "1_1") (pintype "passive"))
      (node (ref "P1") (pin "34") (pinfunction "VGH_34") (pintype "passive"))
    )
    (net (code "84") (name "Net-(P1-VGL)") (class "Default")
      (node (ref "C8") (pin "1") (pinfunction "1_1") (pintype "passive"))
      (node (ref "D1") (pin "A") (pinfunction "A_A") (pintype "passive"))
      (node (ref "P1") (pin "35") (pinfunction "VGL_35") (pintype "passive"))
    )
    (net (code "85") (name "Net-(Q1-D)") (class "Default")
      (node (ref "Q1") (pin "3") (pinfunction "D_3") (pintype "passive"))
      (node (ref "R2") (pin "1") (pinfunction "1_1") (pintype "passive"))
    )
    (net (code "86") (name "Net-(Q1-G)") (class "Default")
      (node (ref "J5") (pin "1") (pinfunction "1_1") (pintype "passive"))
      (node (ref "Q1") (pin "1") (pinfunction "G_1") (pintype "passive"))
      (node (ref "R4") (pin "2") (pinfunction "2_2") (pintype "passive"))
    )
    (net (code "87") (name "VCC") (class "Default")
      (node (ref "BAT1") (pin "+$1") (pinfunction "+_+$1") (pintype "passive"))
      (node (ref "BAT1") (pin "+$2") (pinfunction "+1_+$2") (pintype "passive"))
      (node (ref "BAT2") (pin "+$1") (pinfunction "+_+$1") (pintype "passive"))
      (node (ref "BAT2") (pin "+$2") (pinfunction "+1_+$2") (pintype "passive"))
      (node (ref "BREAKOUT1") (pin "13") (pinfunction "13_13") (pintype "passive"))
      (node (ref "BREAKOUT1") (pin "3") (pinfunction "3_3") (pintype "passive"))
      (node (ref "BREAKOUT1") (pin "30") (pinfunction "30_30") (pintype "passive"))
      (node (ref "BREAKOUT2") (pin "16") (pinfunction "16_16") (pintype "passive"))
      (node (ref "C1") (pin "1") (pinfunction "1_1") (pintype "passive"))
      (node (ref "C2") (pin "1") (pinfunction "1_1") (pintype "passive"))
      (node (ref "C21") (pin "1") (pinfunction "1_1") (pintype "passive"))
      (node (ref "C3") (pin "1") (pinfunction "1_1") (pintype "passive"))
      (node (ref "C4") (pin "1") (pinfunction "1_1") (pintype "passive"))
      (node (ref "J2") (pin "2") (pinfunction "2_2") (pintype "passive"))
      (node (ref "L1") (pin "1-VDD") (pinfunction "VDD_1-VDD") (pintype "bidirectional"))
      (node (ref "LD1") (pin "A") (pinfunction "A_A") (pintype "passive"))
      (node (ref "P1") (pin "31") (pinfunction "VCC_31") (pintype "power_in"))
      (node (ref "P1") (pin "32") (pinfunction "VDD_32") (pintype "power_in"))
      (node (ref "PD1") (pin "C") (pinfunction "C_C") (pintype "passive"))
      (node (ref "PD2") (pin "C") (pinfunction "C_C") (pintype "passive"))
      (node (ref "U1") (pin "13") (pinfunction "VDDA_13") (pintype "power_in"))
      (node (ref "U1") (pin "3") (pinfunction "VDD_2_3") (pintype "power_in"))
      (node (ref "U1") (pin "30") (pinfunction "VDD_3_30") (pintype "power_in"))
      (node (ref "U1") (pin "48") (pinfunction "VDD_48") (pintype "power_in"))
    )
    (net (code "88") (name "unconnected-(L1-DOUT-Pad2-DOUT)") (class "Default")
      (node (ref "L1") (pin "2-DOUT") (pinfunction "DOUT_2-DOUT") (pintype "output"))
    )
    (net (code "89") (name "unconnected-(P1-BORDER-Pad38)") (class "Default")
      (node (ref "P1") (pin "38") (pinfunction "BORDER_38") (pintype "input"))
    )
    (net (code "90") (name "unconnected-(P1-BUSY-Pad2)") (class "Default")
      (node (ref "P1") (pin "2") (pinfunction "BUSY_2") (pintype "output"))
    )
    (net (code "91") (name "unconnected-(P1-C42M-Pad11)") (class "Default")
      (node (ref "P1") (pin "11") (pinfunction "C42M_11") (pintype "no_connect"))
    )
    (net (code "92") (name "unconnected-(P1-C42P-Pad10)") (class "Default")
      (node (ref "P1") (pin "10") (pinfunction "C42P_10") (pintype "no_connect"))
    )
    (net (code "93") (name "unconnected-(P1-PWRON-Pad8)") (class "Default")
      (node (ref "P1") (pin "8") (pinfunction "PWRON_8") (pintype "no_connect"))
    )
    (net (code "94") (name "unconnected-(S1-SH-Pad5)") (class "Default")
      (node (ref "S1") (pin "5") (pinfunction "SH_5") (pintype "passive"))
    )
    (net (code "95") (name "unconnected-(S2-SH-Pad5)") (class "Default")
      (node (ref "S2") (pin "5") (pinfunction "SH_5") (pintype "passive"))
    )
  )
)
